# power_mux-v4.net
KiCad netlist of a schematic drawn in EAGLE
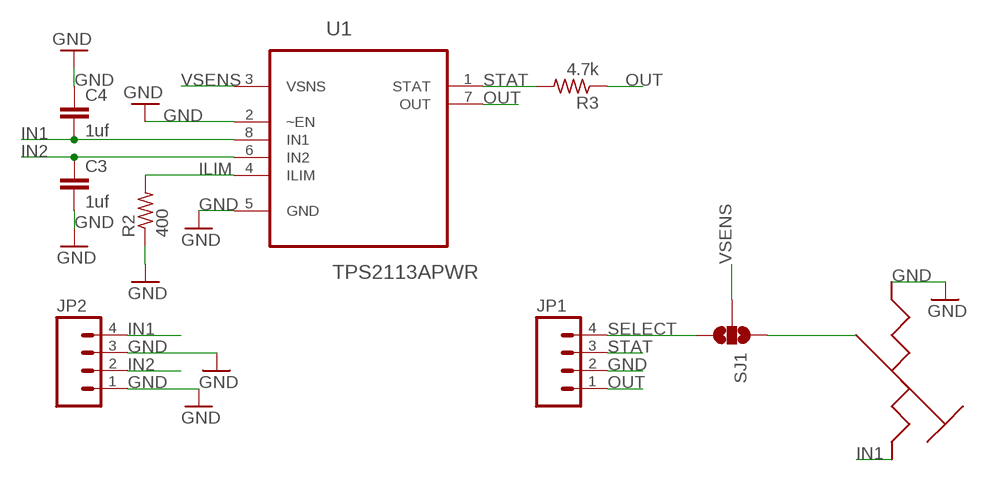
[diagram p0: schematic, sheet 1]

(export (version "E")
  (design (tool "Eeschema 10.0.6"))
  (components
    (comp (ref "C3")
      (value "1uf")
      (footprint "eagle-import:0402-CAP")
      (libsource (lib "eagle-import") (part "CAP0402-CAP"))
    )
    (comp (ref "C4")
      (value "1uf")
      (footprint "eagle-import:0402-CAP")
      (libsource (lib "eagle-import") (part "CAP0402-CAP"))
    )
    (comp (ref "JP1")
      (value "M04PTH")
      (footprint "eagle-import:1X04")
      (libsource (lib "eagle-import") (part "M04PTH"))
    )
    (comp (ref "JP2")
      (value "M04PTH")
      (footprint "eagle-import:1X04")
      (libsource (lib "eagle-import") (part "M04PTH"))
    )
    (comp (ref "R2")
      (value "400")
      (footprint "eagle-import:R0402")
      (libsource (lib "eagle-import") (part "R-US_R0402"))
    )
    (comp (ref "R3")
      (value "4.7k")
      (footprint "eagle-import:R0402")
      (libsource (lib "eagle-import") (part "R-US_R0402"))
    )
    (comp (ref "SJ1")
      (value "SOLDERJUMPER_2WAYPASTE1&2")
      (footprint "eagle-import:SJ_3_PASTE1&2")
      (libsource (lib "eagle-import") (part "SOLDERJUMPER_2WAYPASTE1&2"))
    )
    (comp (ref "U$2")
      (value "TRIMPOT-10K")
      (footprint "eagle-import:TRIMPOT-10K")
      (libsource (lib "eagle-import") (part "TRIMPOT-10K"))
    )
    (comp (ref "U1")
      (value "TPS2113APWR")
      (footprint "eagle-import:SOP65P640X120-8N")
      (libsource (lib "eagle-import") (part "TPS2113APWR"))
    )
  )
  (nets
    (net (code "1") (name "/ILIM") (class "Default")
      (node (ref "R2") (pin "2") (pinfunction "2_2") (pintype "passive"))
      (node (ref "U1") (pin "4") (pinfunction "ILIM_4") (pintype "input"))
    )
    (net (code "2") (name "/IN1") (class "Default")
      (node (ref "C4") (pin "2") (pinfunction "2_2") (pintype "passive"))
      (node (ref "JP2") (pin "4") (pinfunction "4_4") (pintype "passive"))
      (node (ref "U$2") (pin "2") (pinfunction "OUT_2") (pintype "bidirectional"))
      (node (ref "U1") (pin "8") (pinfunction "IN1_8") (pintype "input"))
    )
    (net (code "3") (name "/IN2") (class "Default")
      (node (ref "C3") (pin "1") (pinfunction "1_1") (pintype "passive"))
      (node (ref "JP2") (pin "2") (pinfunction "2_2") (pintype "passive"))
      (node (ref "U1") (pin "6") (pinfunction "IN2_6") (pintype "input"))
    )
    (net (code "4") (name "/OUT") (class "Default")
      (node (ref "JP1") (pin "1") (pinfunction "1_1") (pintype "passive"))
      (node (ref "R3") (pin "1") (pinfunction "1_1") (pintype "passive"))
      (node (ref "U1") (pin "7") (pinfunction "OUT_7") (pintype "output"))
    )
    (net (code "5") (name "/SELECT") (class "Default")
      (node (ref "JP1") (pin "4") (pinfunction "4_4") (pintype "passive"))
      (node (ref "SJ1") (pin "3") (pinfunction "3_3") (pintype "passive"))
    )
    (net (code "6") (name "/STAT") (class "Default")
      (node (ref "JP1") (pin "3") (pinfunction "3_3") (pintype "passive"))
      (node (ref "R3") (pin "2") (pinfunction "2_2") (pintype "passive"))
      (node (ref "U1") (pin "1") (pinfunction "STAT_1") (pintype "output"))
    )
    (net (code "7") (name "/VSENS") (class "Default")
      (node (ref "SJ1") (pin "2") (pinfunction "2_2") (pintype "passive"))
      (node (ref "U1") (pin "3") (pinfunction "VSNS_3") (pintype "power_in"))
    )
    (net (code "8") (name "GND") (class "Default")
      (node (ref "C3") (pin "2") (pinfunction "2_2") (pintype "passive"))
      (node (ref "C4") (pin "1") (pinfunction "1_1") (pintype "passive"))
      (node (ref "JP1") (pin "2") (pinfunction "2_2") (pintype "passive"))
      (node (ref "JP2") (pin "1") (pinfunction "1_1") (pintype "passive"))
      (node (ref "JP2") (pin "3") (pinfunction "3_3") (pintype "passive"))
      (node (ref "R2") (pin "1") (pinfunction "1_1") (pintype "passive"))
      (node (ref "U$2") (pin "1") (pinfunction "IN_1") (pintype "bidirectional"))
      (node (ref "U1") (pin "2") (pinfunction "~{EN}_2") (pintype "input"))
      (node (ref "U1") (pin "5") (pinfunction "GND_5") (pintype "passive"))
    )
    (net (code "9") (name "Net-(U$2-W)") (class "Default")
      (node (ref "SJ1") (pin "1") (pinfunction "1_1") (pintype "passive"))
      (node (ref "U$2") (pin "3") (pinfunction "W_3") (pintype "bidirectional"))
    )
  )
)
